# sao-45.net
KiCad netlist of a schematic drawn in EAGLE
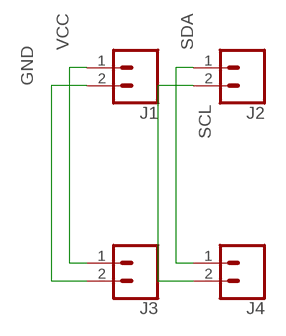
[diagram p0: schematic, sheet 1]

(export (version "E")
  (design (tool "Eeschema 10.0.6"))
  (components
    (comp (ref "J1")
      (value "CONN_02LOCK")
      (footprint "eagle-import:1X02_LOCK")
      (libsource (lib "eagle-import") (part "CONN_02LOCK"))
    )
    (comp (ref "J2")
      (value "CONN_02LOCK")
      (footprint "eagle-import:1X02_LOCK")
      (libsource (lib "eagle-import") (part "CONN_02LOCK"))
    )
    (comp (ref "J3")
      (value "CONN_02LOCK")
      (footprint "eagle-import:1X02_LOCK")
      (libsource (lib "eagle-import") (part "CONN_02LOCK"))
    )
    (comp (ref "J4")
      (value "CONN_02LOCK")
      (footprint "eagle-import:1X02_LOCK")
      (libsource (lib "eagle-import") (part "CONN_02LOCK"))
    )
  )
  (nets
    (net (code "1") (name "/GND") (class "Default")
      (node (ref "J1") (pin "2") (pinfunction "2_2") (pintype "passive"))
      (node (ref "J3") (pin "2") (pinfunction "2_2") (pintype "passive"))
    )
    (net (code "2") (name "/SCL") (class "Default")
      (node (ref "J2") (pin "2") (pinfunction "2_2") (pintype "passive"))
      (node (ref "J4") (pin "2") (pinfunction "2_2") (pintype "passive"))
    )
    (net (code "3") (name "/SDA") (class "Default")
      (node (ref "J2") (pin "1") (pinfunction "1_1") (pintype "passive"))
      (node (ref "J4") (pin "1") (pinfunction "1_1") (pintype "passive"))
    )
    (net (code "4") (name "/VCC") (class "Default")
      (node (ref "J1") (pin "1") (pinfunction "1_1") (pintype "passive"))
      (node (ref "J3") (pin "1") (pinfunction "1_1") (pintype "passive"))
    )
  )
)
